# wagband_schematic.net
KiCad netlist of a schematic drawn in EAGLE
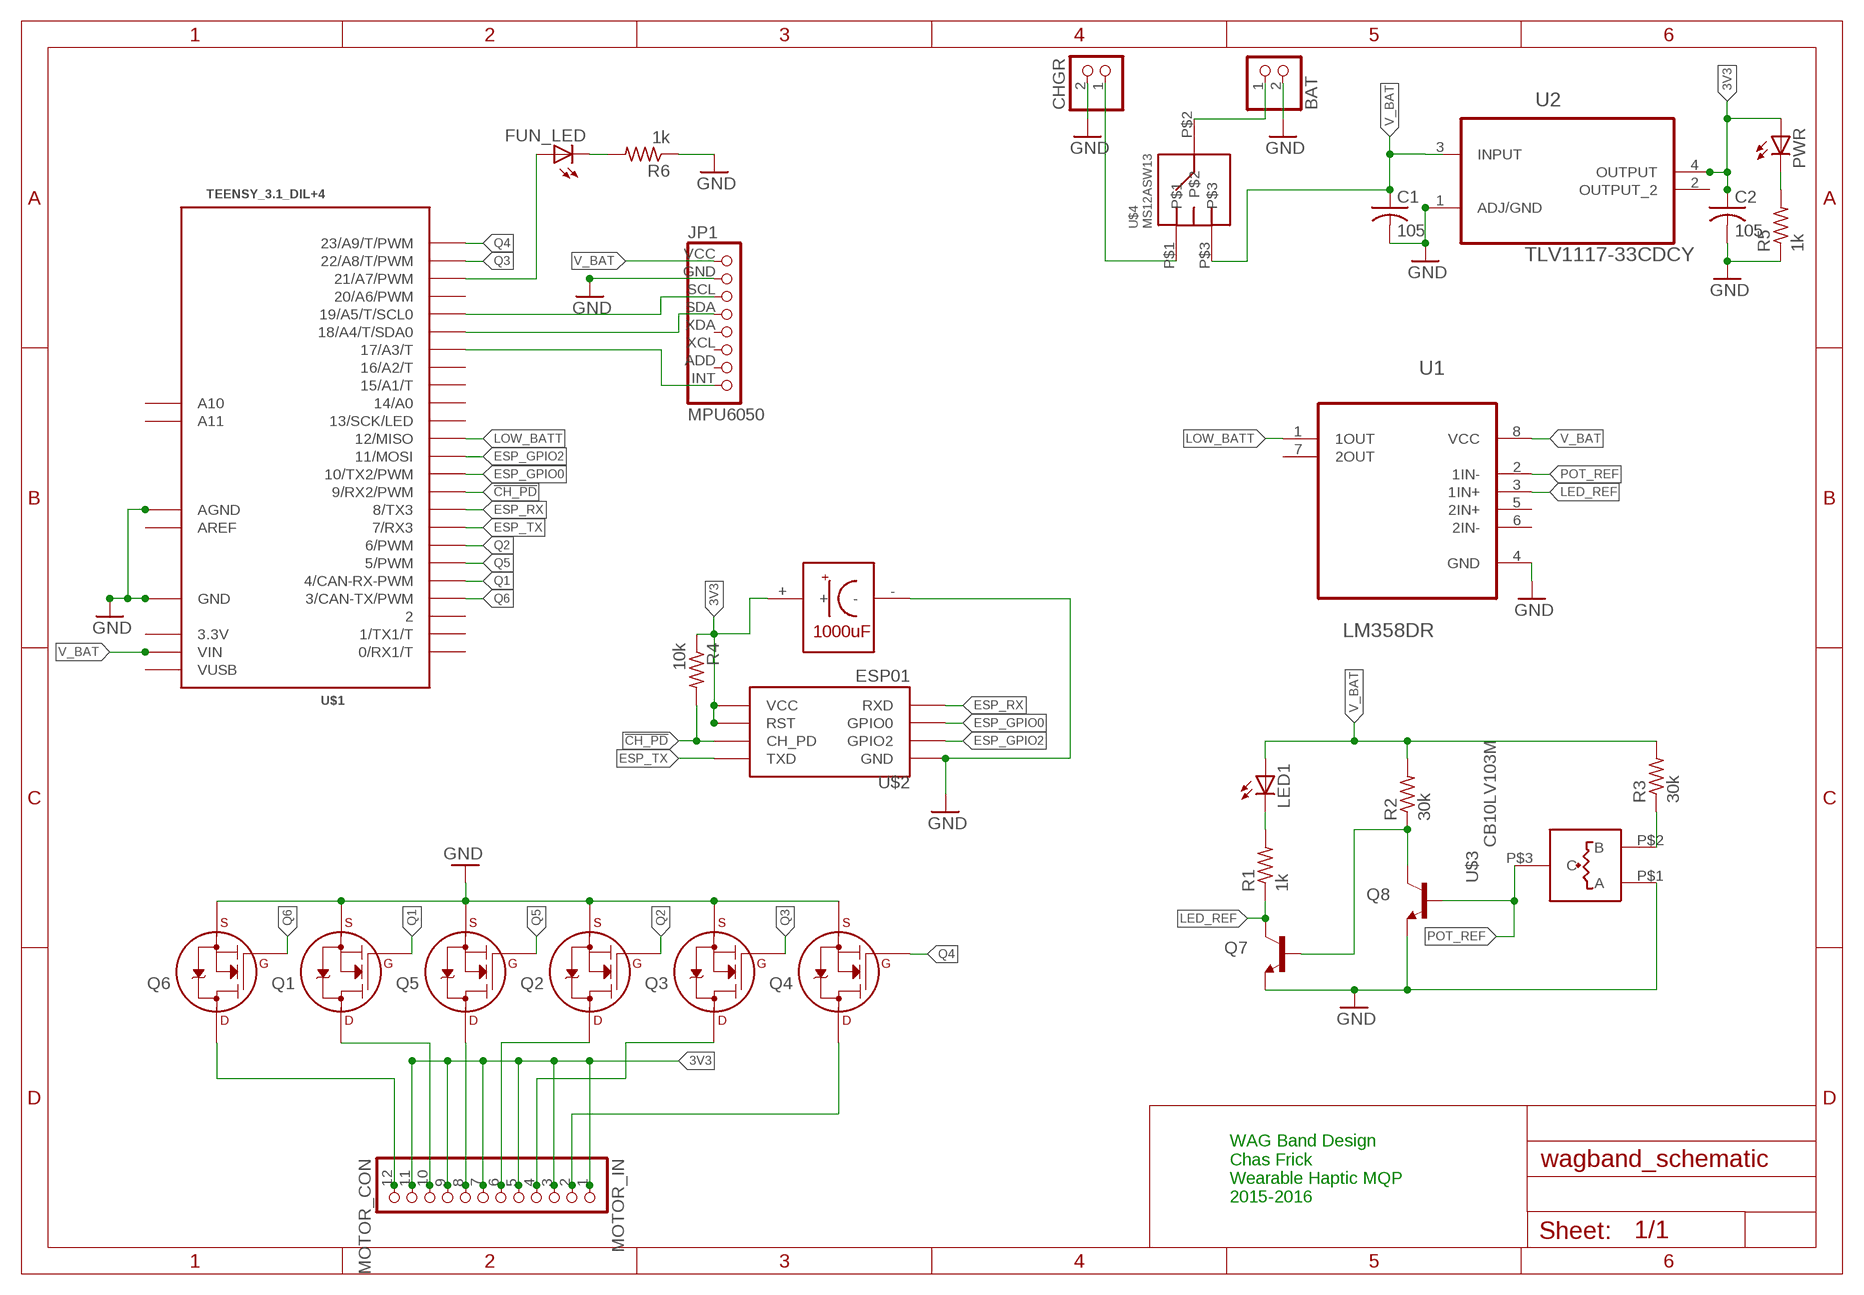
[diagram p0: schematic, sheet 1]

(export (version "E")
  (design (tool "Eeschema 10.0.6"))
  (components
    (comp (ref "BAT")
      (value "JST_2PIN-THM-RA")
      (footprint "eagle-import:JST-PH-2-THM-RA")
      (libsource (lib "eagle-import") (part "JST_2PIN-THM-RA"))
    )
    (comp (ref "C1")
      (value "105")
      (footprint "eagle-import:C0805K")
      (libsource (lib "eagle-import") (part "C-USC0805K"))
    )
    (comp (ref "C2")
      (value "105")
      (footprint "eagle-import:C0805K")
      (libsource (lib "eagle-import") (part "C-USC0805K"))
    )
    (comp (ref "CHGR")
      (value "JST_2PIN-THM-RA")
      (footprint "eagle-import:JST-PH-2-THM-RA")
      (libsource (lib "eagle-import") (part "JST_2PIN-THM-RA"))
    )
    (comp (ref "FUN_LED")
      (value "LED5MM")
      (footprint "eagle-import:LED5MM")
      (libsource (lib "eagle-import") (part "LED5MM"))
    )
    (comp (ref "JP1")
      (value "MPU6050")
      (footprint "eagle-import:MPU6050")
      (libsource (lib "eagle-import") (part "MPU6050_BREAKOUT"))
    )
    (comp (ref "LED1")
      (value "LED5MM")
      (footprint "eagle-import:LED5MM")
      (libsource (lib "eagle-import") (part "LED5MM"))
    )
    (comp (ref "MOTOR_IN")
      (value "MOTOR_CON")
      (footprint "eagle-import:1X12")
      (libsource (lib "eagle-import") (part "PINHD-1X12"))
    )
    (comp (ref "PWR")
      (value "LED5MM")
      (footprint "eagle-import:LED5MM")
      (libsource (lib "eagle-import") (part "LED5MM"))
    )
    (comp (ref "Q1")
      (value "2N7000_SOT23")
      (footprint "eagle-import:SOT-23")
      (libsource (lib "eagle-import") (part "2N700_SOT230"))
    )
    (comp (ref "Q2")
      (value "2N7000_SOT23")
      (footprint "eagle-import:SOT-23")
      (libsource (lib "eagle-import") (part "2N700_SOT230"))
    )
    (comp (ref "Q3")
      (value "2N7000_SOT23")
      (footprint "eagle-import:SOT-23")
      (libsource (lib "eagle-import") (part "2N700_SOT230"))
    )
    (comp (ref "Q4")
      (value "2N7000_SOT23")
      (footprint "eagle-import:SOT-23")
      (libsource (lib "eagle-import") (part "2N700_SOT230"))
    )
    (comp (ref "Q5")
      (value "2N7000_SOT23")
      (footprint "eagle-import:SOT-23")
      (libsource (lib "eagle-import") (part "2N700_SOT230"))
    )
    (comp (ref "Q6")
      (value "2N7000_SOT23")
      (footprint "eagle-import:SOT-23")
      (libsource (lib "eagle-import") (part "2N700_SOT230"))
    )
    (comp (ref "Q7")
      (value "TRANSISTOR_NPNMMBT3904")
      (footprint "eagle-import:SOT-23")
      (libsource (lib "eagle-import") (part "TRANSISTOR_NPNMMBT3904"))
    )
    (comp (ref "Q8")
      (value "TRANSISTOR_NPNMMBT3904")
      (footprint "eagle-import:SOT-23")
      (libsource (lib "eagle-import") (part "TRANSISTOR_NPNMMBT3904"))
    )
    (comp (ref "R1")
      (value "1k")
      (footprint "eagle-import:R0402")
      (libsource (lib "eagle-import") (part "R-US_R0402"))
    )
    (comp (ref "R2")
      (value "30k")
      (footprint "eagle-import:R1206")
      (libsource (lib "eagle-import") (part "R-US_R1206"))
    )
    (comp (ref "R3")
      (value "30k")
      (footprint "eagle-import:R1206")
      (libsource (lib "eagle-import") (part "R-US_R1206"))
    )
    (comp (ref "R4")
      (value "10k")
      (footprint "eagle-import:R1206")
      (libsource (lib "eagle-import") (part "R-US_R1206"))
    )
    (comp (ref "R5")
      (value "1k")
      (footprint "eagle-import:R0402")
      (libsource (lib "eagle-import") (part "R-US_R0402"))
    )
    (comp (ref "R6")
      (value "1k")
      (footprint "eagle-import:R0402")
      (libsource (lib "eagle-import") (part "R-US_R0402"))
    )
    (comp (ref "U$1")
      (value "TEENSY_3.1_DIL+4")
      (footprint "eagle-import:TEENSY3-DIL+4")
      (libsource (lib "eagle-import") (part "TEENSY_3.1_DIL+4"))
    )
    (comp (ref "U$2")
      (value "ESP01")
      (footprint "eagle-import:ESP01")
      (libsource (lib "eagle-import") (part "ESP01"))
    )
    (comp (ref "U$3")
      (value "CB10LV103M")
      (footprint "eagle-import:CB10")
      (libsource (lib "eagle-import") (part "CB10LV103M"))
    )
    (comp (ref "U$4")
      (value "MS12ASW13")
      (footprint "eagle-import:SPDT")
      (libsource (lib "eagle-import") (part "MS12ASW13"))
    )
    (comp (ref "U$5")
      (value "TZVCAP")
      (footprint "eagle-import:TZV1000M")
      (libsource (lib "eagle-import") (part "TZVCAP"))
    )
    (comp (ref "U1")
      (value "LM358DR")
      (footprint "eagle-import:SOIC127P600X175-8N")
      (libsource (lib "eagle-import") (part "LM358DR"))
    )
    (comp (ref "U2")
      (value "TLV1117-33CDCY")
      (footprint "eagle-import:SOT230P700X180-4N")
      (libsource (lib "eagle-import") (part "TLV1117-33CDCY"))
    )
  )
  (nets
    (net (code "1") (name "/3.3V") (class "Default")
      (node (ref "U$1") (pin "3.3V") (pinfunction "3.3V_3.3V") (pintype "power_in"))
    )
    (net (code "2") (name "/AREF") (class "Default")
      (node (ref "U$1") (pin "AREF") (pinfunction "AREF_AREF") (pintype "power_in"))
    )
    (net (code "3") (name "/VUSB") (class "Default")
      (node (ref "U$1") (pin "VUSB") (pinfunction "VUSB_VUSB") (pintype "power_in"))
    )
    (net (code "4") (name "/~{CH_PD}") (class "Default")
      (node (ref "R4") (pin "2") (pinfunction "2_2") (pintype "passive"))
      (node (ref "U$1") (pin "9") (pinfunction "9/RX2/PWM_9") (pintype "bidirectional"))
      (node (ref "U$2") (pin "CH_PD") (pinfunction "CH_PD_CH_PD") (pintype "bidirectional"))
    )
    (net (code "5") (name "3V3") (class "Default")
      (node (ref "C2") (pin "1") (pinfunction "1_1") (pintype "passive"))
      (node (ref "MOTOR_IN") (pin "1") (pinfunction "1_1") (pintype "passive"))
      (node (ref "MOTOR_IN") (pin "11") (pinfunction "11_11") (pintype "passive"))
      (node (ref "MOTOR_IN") (pin "3") (pinfunction "3_3") (pintype "passive"))
      (node (ref "MOTOR_IN") (pin "5") (pinfunction "5_5") (pintype "passive"))
      (node (ref "MOTOR_IN") (pin "7") (pinfunction "7_7") (pintype "passive"))
      (node (ref "MOTOR_IN") (pin "9") (pinfunction "9_9") (pintype "passive"))
      (node (ref "PWR") (pin "A") (pinfunction "A_A") (pintype "passive"))
      (node (ref "R4") (pin "1") (pinfunction "1_1") (pintype "passive"))
      (node (ref "U$2") (pin "RST") (pinfunction "RST_RST") (pintype "bidirectional"))
      (node (ref "U$2") (pin "VCC") (pinfunction "VCC_VCC") (pintype "bidirectional"))
      (node (ref "U$5") (pin "+") (pinfunction "+_+") (pintype "bidirectional"))
      (node (ref "U2") (pin "4") (pinfunction "OUTPUT_4") (pintype "output"))
    )
    (net (code "6") (name "ESP_GPIO0") (class "Default")
      (node (ref "U$1") (pin "10") (pinfunction "10/TX2/PWM_10") (pintype "bidirectional"))
      (node (ref "U$2") (pin "GPIO0") (pinfunction "GPIO0_GPIO0") (pintype "bidirectional"))
    )
    (net (code "7") (name "ESP_GPIO2") (class "Default")
      (node (ref "U$1") (pin "11") (pinfunction "11/MOSI_11") (pintype "bidirectional"))
      (node (ref "U$2") (pin "GPIO2") (pinfunction "GPIO2_GPIO2") (pintype "bidirectional"))
    )
    (net (code "8") (name "ESP_RX") (class "Default")
      (node (ref "U$1") (pin "8") (pinfunction "8/TX3_8") (pintype "bidirectional"))
      (node (ref "U$2") (pin "RX") (pinfunction "RXD_RX") (pintype "bidirectional"))
    )
    (net (code "9") (name "ESP_TX") (class "Default")
      (node (ref "U$1") (pin "7") (pinfunction "7/RX3_7") (pintype "bidirectional"))
      (node (ref "U$2") (pin "TX") (pinfunction "TXD_TX") (pintype "bidirectional"))
    )
    (net (code "10") (name "GND") (class "Default")
      (node (ref "BAT") (pin "2") (pinfunction "1_2") (pintype "passive"))
      (node (ref "C1") (pin "2") (pinfunction "2_2") (pintype "passive"))
      (node (ref "C2") (pin "2") (pinfunction "2_2") (pintype "passive"))
      (node (ref "CHGR") (pin "2") (pinfunction "1_2") (pintype "passive"))
      (node (ref "JP1") (pin "GND") (pinfunction "GND_GND") (pintype "passive"))
      (node (ref "Q1") (pin "2") (pinfunction "S_2") (pintype "bidirectional"))
      (node (ref "Q2") (pin "2") (pinfunction "S_2") (pintype "bidirectional"))
      (node (ref "Q3") (pin "2") (pinfunction "S_2") (pintype "bidirectional"))
      (node (ref "Q4") (pin "2") (pinfunction "S_2") (pintype "bidirectional"))
      (node (ref "Q5") (pin "2") (pinfunction "S_2") (pintype "bidirectional"))
      (node (ref "Q6") (pin "2") (pinfunction "S_2") (pintype "bidirectional"))
      (node (ref "Q7") (pin "2") (pinfunction "E_2") (pintype "passive"))
      (node (ref "Q8") (pin "2") (pinfunction "E_2") (pintype "passive"))
      (node (ref "R5") (pin "1") (pinfunction "1_1") (pintype "passive"))
      (node (ref "R6") (pin "1") (pinfunction "1_1") (pintype "passive"))
      (node (ref "U$1") (pin "AGND") (pinfunction "AGND_AGND") (pintype "power_in"))
      (node (ref "U$1") (pin "GND") (pinfunction "GND_GND") (pintype "power_in"))
      (node (ref "U$2") (pin "GND") (pinfunction "GND_GND") (pintype "bidirectional"))
      (node (ref "U$3") (pin "P$1") (pinfunction "A_P$1") (pintype "bidirectional"))
      (node (ref "U$5") (pin "-") (pinfunction "-_-") (pintype "bidirectional"))
      (node (ref "U1") (pin "4") (pinfunction "GND_4") (pintype "passive"))
      (node (ref "U2") (pin "1") (pinfunction "ADJ/GND_1") (pintype "input"))
    )
    (net (code "11") (name "LED_REF") (class "Default")
      (node (ref "Q7") (pin "3") (pinfunction "C_3") (pintype "passive"))
      (node (ref "R1") (pin "1") (pinfunction "1_1") (pintype "passive"))
      (node (ref "U1") (pin "3") (pinfunction "1IN+_3") (pintype "input"))
    )
    (net (code "12") (name "LOW_BATT") (class "Default")
      (node (ref "U$1") (pin "12") (pinfunction "12/MISO_12") (pintype "bidirectional"))
      (node (ref "U1") (pin "1") (pinfunction "1OUT_1") (pintype "output"))
    )
    (net (code "13") (name "Net-(BAT-2)") (class "Default")
      (node (ref "BAT") (pin "1") (pinfunction "2_1") (pintype "passive"))
      (node (ref "U$4") (pin "P$2") (pinfunction "P$2_P$2") (pintype "bidirectional"))
    )
    (net (code "14") (name "Net-(CHGR-2)") (class "Default")
      (node (ref "CHGR") (pin "1") (pinfunction "2_1") (pintype "passive"))
      (node (ref "U$4") (pin "P$1") (pinfunction "P$1_P$1") (pintype "bidirectional"))
    )
    (net (code "15") (name "Net-(FUN_LED-C)") (class "Default")
      (node (ref "FUN_LED") (pin "K") (pinfunction "C_K") (pintype "passive"))
      (node (ref "R6") (pin "2") (pinfunction "2_2") (pintype "passive"))
    )
    (net (code "16") (name "Net-(LED1-C)") (class "Default")
      (node (ref "LED1") (pin "K") (pinfunction "C_K") (pintype "passive"))
      (node (ref "R1") (pin "2") (pinfunction "2_2") (pintype "passive"))
    )
    (net (code "17") (name "Net-(PWR-C)") (class "Default")
      (node (ref "PWR") (pin "K") (pinfunction "C_K") (pintype "passive"))
      (node (ref "R5") (pin "2") (pinfunction "2_2") (pintype "passive"))
    )
    (net (code "18") (name "Net-(Q1-D)") (class "Default")
      (node (ref "MOTOR_IN") (pin "10") (pinfunction "10_10") (pintype "passive"))
      (node (ref "Q1") (pin "3") (pinfunction "D_3") (pintype "bidirectional"))
    )
    (net (code "19") (name "Net-(Q2-D)") (class "Default")
      (node (ref "MOTOR_IN") (pin "6") (pinfunction "6_6") (pintype "passive"))
      (node (ref "Q2") (pin "3") (pinfunction "D_3") (pintype "bidirectional"))
    )
    (net (code "20") (name "Net-(Q3-D)") (class "Default")
      (node (ref "MOTOR_IN") (pin "4") (pinfunction "4_4") (pintype "passive"))
      (node (ref "Q3") (pin "3") (pinfunction "D_3") (pintype "bidirectional"))
    )
    (net (code "21") (name "Net-(Q4-D)") (class "Default")
      (node (ref "MOTOR_IN") (pin "2") (pinfunction "2_2") (pintype "passive"))
      (node (ref "Q4") (pin "3") (pinfunction "D_3") (pintype "bidirectional"))
    )
    (net (code "22") (name "Net-(Q5-D)") (class "Default")
      (node (ref "MOTOR_IN") (pin "8") (pinfunction "8_8") (pintype "passive"))
      (node (ref "Q5") (pin "3") (pinfunction "D_3") (pintype "bidirectional"))
    )
    (net (code "23") (name "Net-(Q6-D)") (class "Default")
      (node (ref "MOTOR_IN") (pin "12") (pinfunction "12_12") (pintype "passive"))
      (node (ref "Q6") (pin "3") (pinfunction "D_3") (pintype "bidirectional"))
    )
    (net (code "24") (name "Net-(Q7-B)") (class "Default")
      (node (ref "Q7") (pin "1") (pinfunction "B_1") (pintype "passive"))
      (node (ref "Q8") (pin "3") (pinfunction "C_3") (pintype "passive"))
      (node (ref "R2") (pin "1") (pinfunction "1_1") (pintype "passive"))
    )
    (net (code "25") (name "Net-(U$1-17{slash}A3{slash}T)") (class "Default")
      (node (ref "JP1") (pin "INT") (pinfunction "INT_INT") (pintype "passive"))
      (node (ref "U$1") (pin "17/A3") (pinfunction "17/A3/T_17/A3") (pintype "bidirectional"))
    )
    (net (code "26") (name "Net-(U$1-18{slash}A4{slash}T{slash}SDA0)") (class "Default")
      (node (ref "JP1") (pin "SDA") (pinfunction "SDA_SDA") (pintype "passive"))
      (node (ref "U$1") (pin "18/A4") (pinfunction "18/A4/T/SDA0_18/A4") (pintype "bidirectional"))
    )
    (net (code "27") (name "Net-(U$1-19{slash}A5{slash}T{slash}SCL0)") (class "Default")
      (node (ref "JP1") (pin "SCL") (pinfunction "SCL_SCL") (pintype "passive"))
      (node (ref "U$1") (pin "19/A5") (pinfunction "19/A5/T/SCL0_19/A5") (pintype "bidirectional"))
    )
    (net (code "28") (name "Net-(U$1-21{slash}A7{slash}PWM)") (class "Default")
      (node (ref "FUN_LED") (pin "A") (pinfunction "A_A") (pintype "passive"))
      (node (ref "U$1") (pin "21/A7") (pinfunction "21/A7/PWM_21/A7") (pintype "bidirectional"))
    )
    (net (code "29") (name "Net-(U$3-B)") (class "Default")
      (node (ref "R3") (pin "1") (pinfunction "1_1") (pintype "passive"))
      (node (ref "U$3") (pin "P$2") (pinfunction "B_P$2") (pintype "bidirectional"))
    )
    (net (code "30") (name "POT_REF") (class "Default")
      (node (ref "Q8") (pin "1") (pinfunction "B_1") (pintype "passive"))
      (node (ref "U$3") (pin "P$3") (pinfunction "C_P$3") (pintype "bidirectional"))
      (node (ref "U1") (pin "2") (pinfunction "1IN-_2") (pintype "input"))
    )
    (net (code "31") (name "Q1") (class "Default")
      (node (ref "Q1") (pin "1") (pinfunction "G_1") (pintype "tri_state"))
      (node (ref "U$1") (pin "4") (pinfunction "4/CAN-RX-PWM_4") (pintype "bidirectional"))
    )
    (net (code "32") (name "Q2") (class "Default")
      (node (ref "Q2") (pin "1") (pinfunction "G_1") (pintype "tri_state"))
      (node (ref "U$1") (pin "6") (pinfunction "6/PWM_6") (pintype "bidirectional"))
    )
    (net (code "33") (name "Q3") (class "Default")
      (node (ref "Q3") (pin "1") (pinfunction "G_1") (pintype "tri_state"))
      (node (ref "U$1") (pin "22/A8") (pinfunction "22/A8/T/PWM_22/A8") (pintype "bidirectional"))
    )
    (net (code "34") (name "Q4") (class "Default")
      (node (ref "Q4") (pin "1") (pinfunction "G_1") (pintype "tri_state"))
      (node (ref "U$1") (pin "23/A9") (pinfunction "23/A9/T/PWM_23/A9") (pintype "bidirectional"))
    )
    (net (code "35") (name "Q5") (class "Default")
      (node (ref "Q5") (pin "1") (pinfunction "G_1") (pintype "tri_state"))
      (node (ref "U$1") (pin "5") (pinfunction "5/PWM_5") (pintype "bidirectional"))
    )
    (net (code "36") (name "Q6") (class "Default")
      (node (ref "Q6") (pin "1") (pinfunction "G_1") (pintype "tri_state"))
      (node (ref "U$1") (pin "3") (pinfunction "3/CAN-TX/PWM_3") (pintype "bidirectional"))
    )
    (net (code "37") (name "V_BAT") (class "Default")
      (node (ref "C1") (pin "1") (pinfunction "1_1") (pintype "passive"))
      (node (ref "JP1") (pin "VCC") (pinfunction "VCC_VCC") (pintype "passive"))
      (node (ref "LED1") (pin "A") (pinfunction "A_A") (pintype "passive"))
      (node (ref "R2") (pin "2") (pinfunction "2_2") (pintype "passive"))
      (node (ref "R3") (pin "2") (pinfunction "2_2") (pintype "passive"))
      (node (ref "U$1") (pin "VIN") (pinfunction "VIN_VIN") (pintype "power_in"))
      (node (ref "U$4") (pin "P$3") (pinfunction "P$3_P$3") (pintype "bidirectional"))
      (node (ref "U1") (pin "8") (pinfunction "VCC_8") (pintype "power_in"))
      (node (ref "U2") (pin "3") (pinfunction "INPUT_3") (pintype "input"))
    )
    (net (code "38") (name "unconnected-(JP1-PadADD)") (class "Default")
      (node (ref "JP1") (pin "ADD") (pinfunction "ADD_ADD") (pintype "passive"))
    )
    (net (code "39") (name "unconnected-(JP1-PadXCL)") (class "Default")
      (node (ref "JP1") (pin "XCL") (pinfunction "XCL_XCL") (pintype "passive"))
    )
    (net (code "40") (name "unconnected-(JP1-PadXDA)") (class "Default")
      (node (ref "JP1") (pin "XDA") (pinfunction "XDA_XDA") (pintype "passive"))
    )
    (net (code "41") (name "unconnected-(U$1-0{slash}RX1{slash}T-Pad0)") (class "Default")
      (node (ref "U$1") (pin "0") (pinfunction "0/RX1/T_0") (pintype "bidirectional"))
    )
    (net (code "42") (name "unconnected-(U$1-1{slash}TX1{slash}T-Pad1)") (class "Default")
      (node (ref "U$1") (pin "1") (pinfunction "1/TX1/T_1") (pintype "bidirectional"))
    )
    (net (code "43") (name "unconnected-(U$1-13{slash}SCK{slash}LED-Pad13)") (class "Default")
      (node (ref "U$1") (pin "13") (pinfunction "13/SCK/LED_13") (pintype "bidirectional"))
    )
    (net (code "44") (name "unconnected-(U$1-15{slash}A1{slash}T-Pad15{slash}A1)") (class "Default")
      (node (ref "U$1") (pin "15/A1") (pinfunction "15/A1/T_15/A1") (pintype "bidirectional"))
    )
    (net (code "45") (name "unconnected-(U$1-16{slash}A2{slash}T-Pad16{slash}A2)") (class "Default")
      (node (ref "U$1") (pin "16/A2") (pinfunction "16/A2/T_16/A2") (pintype "bidirectional"))
    )
    (net (code "46") (name "unconnected-(U$1-20{slash}A6{slash}PWM-Pad20{slash}A6)") (class "Default")
      (node (ref "U$1") (pin "20/A6") (pinfunction "20/A6/PWM_20/A6") (pintype "bidirectional"))
    )
    (net (code "47") (name "unconnected-(U$1-Pad2)") (class "Default")
      (node (ref "U$1") (pin "2") (pinfunction "2_2") (pintype "bidirectional"))
    )
    (net (code "48") (name "unconnected-(U$1-Pad14{slash}A0)") (class "Default")
      (node (ref "U$1") (pin "14/A0") (pinfunction "14/A0_14/A0") (pintype "bidirectional"))
    )
    (net (code "49") (name "unconnected-(U$1-PadA10)") (class "Default")
      (node (ref "U$1") (pin "A10") (pinfunction "A10_A10") (pintype "bidirectional"))
    )
    (net (code "50") (name "unconnected-(U$1-PadA11)") (class "Default")
      (node (ref "U$1") (pin "A11") (pinfunction "A11_A11") (pintype "bidirectional"))
    )
    (net (code "51") (name "unconnected-(U1-2IN+-Pad5)") (class "Default")
      (node (ref "U1") (pin "5") (pinfunction "2IN+_5") (pintype "input"))
    )
    (net (code "52") (name "unconnected-(U1-2IN--Pad6)") (class "Default")
      (node (ref "U1") (pin "6") (pinfunction "2IN-_6") (pintype "input"))
    )
    (net (code "53") (name "unconnected-(U1-2OUT-Pad7)") (class "Default")
      (node (ref "U1") (pin "7") (pinfunction "2OUT_7") (pintype "output"))
    )
    (net (code "54") (name "unconnected-(U2-OUTPUT_2-Pad2)") (class "Default")
      (node (ref "U2") (pin "2") (pinfunction "OUTPUT_2_2") (pintype "output"))
    )
  )
)
